# FPGA_POWER.net
KiCad netlist of a schematic drawn in Altium Designer
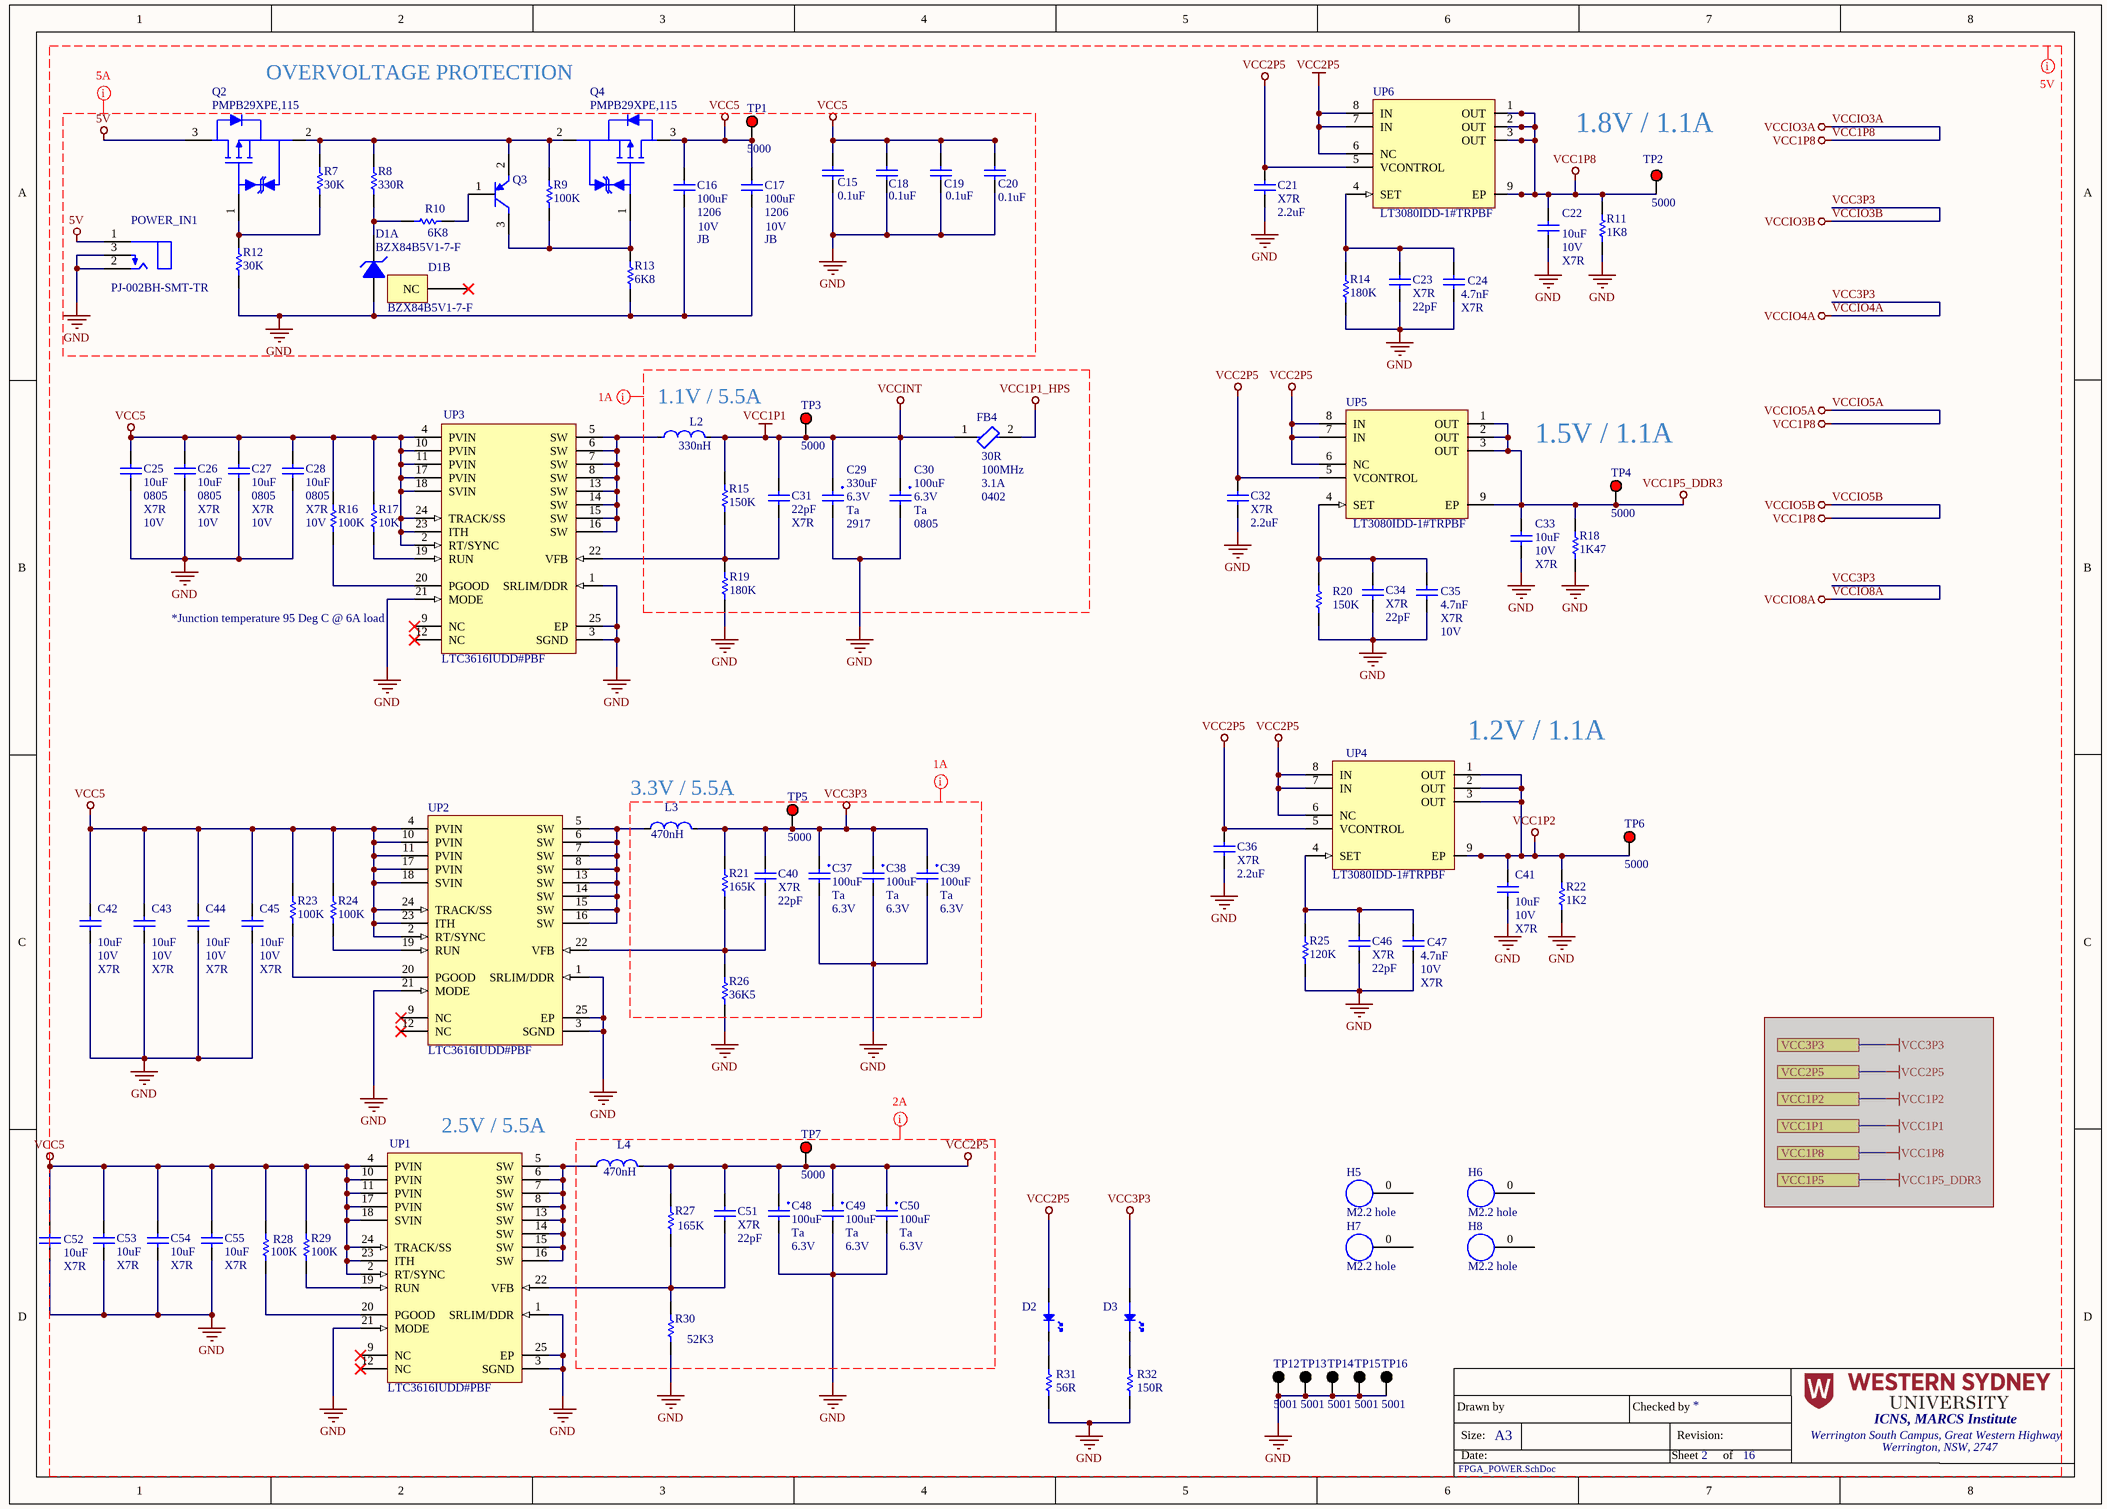
[diagram p0: FPGA_POWER.SchDoc]

(export (version "E")
  (design (tool "Eeschema 10.0.6"))
  (components
    (comp (ref "C15")
      (value "0.1uF")
      (footprint "CAP 0402 (1005)")
      (description "Cap Ceramic 0.1uF 10V X7R 20% SMD 0402 125°C Paper T/R")
      (fields
        (field (name "TOLERANCE") "20%")
        (field (name "Comment") "C0402C104M8RACTU")
        (field (name "SOURCE") "ICNS_PropheseeLib.SchLib")
      )
      (libsource (lib "Western Sydney University - ICNS") (part "Symbol"))
    )
    (comp (ref "C16")
      (value "100uF")
      (footprint "FP-C3216-160-0_3-IPC_A")
      (description "Cap Ceramic 100uF 10 V JB ±20 % Tolerance SMT 1206 Multilayer Ceramic Capacitor C Series")
      (fields
        (field (name "CASE/PACKAGE") "1206")
        (field (name "TOLERANCE") "20%")
        (field (name "VOLTAGE RATING") "10V")
        (field (name "DIELECTRIC") "JB")
        (field (name "Comment") "C3216JB1A107M160AC")
        (field (name "SOURCE") "ICNS_PropheseeLib.SchLib")
      )
      (libsource (lib "Western Sydney University - ICNS") (part "Symbol"))
    )
    (comp (ref "C17")
      (value "100uF")
      (footprint "FP-C3216-160-0_3-IPC_A")
      (description "Cap Ceramic 100uF 10 V JB ±20 % Tolerance SMT 1206 Multilayer Ceramic Capacitor C Series")
      (fields
        (field (name "CASE/PACKAGE") "1206")
        (field (name "TOLERANCE") "20%")
        (field (name "VOLTAGE RATING") "10V")
        (field (name "DIELECTRIC") "JB")
        (field (name "Comment") "C3216JB1A107M160AC")
        (field (name "SOURCE") "ICNS_PropheseeLib.SchLib")
      )
      (libsource (lib "Western Sydney University - ICNS") (part "Symbol"))
    )
    (comp (ref "C18")
      (value "0.1uF")
      (footprint "CAP 0402 (1005)")
      (description "Cap Ceramic 0.1uF 10V X7R 20% SMD 0402 125°C Paper T/R")
      (fields
        (field (name "TOLERANCE") "20%")
        (field (name "Comment") "C0402C104M8RACTU")
        (field (name "SOURCE") "ICNS_PropheseeLib.SchLib")
      )
      (libsource (lib "Western Sydney University - ICNS") (part "Symbol"))
    )
    (comp (ref "C19")
      (value "0.1uF")
      (footprint "CAP 0402 (1005)")
      (description "Cap Ceramic 0.1uF 10V X7R 20% SMD 0402 125°C Paper T/R")
      (fields
        (field (name "TOLERANCE") "20%")
        (field (name "Comment") "C0402C104M8RACTU")
        (field (name "SOURCE") "ICNS_PropheseeLib.SchLib")
      )
      (libsource (lib "Western Sydney University - ICNS") (part "Symbol"))
    )
    (comp (ref "C20")
      (value "0.1uF")
      (footprint "CAP 0402 (1005)")
      (description "Cap Ceramic 0.1uF 10V X7R 20% SMD 0402 125°C Paper T/R")
      (fields
        (field (name "TOLERANCE") "20%")
        (field (name "Comment") "C0402C104M8RACTU")
        (field (name "SOURCE") "ICNS_PropheseeLib.SchLib")
      )
      (libsource (lib "Western Sydney University - ICNS") (part "Symbol"))
    )
    (comp (ref "C21")
      (value "GRM155Z71A225KE01D")
      (footprint "CAP 0402 (1005)")
      (description "Multilayer Ceramic Capacitor 0402 10V X7R 2.2uf 10%Tol paper")
      (fields
        (field (name "DIELECTRIC") "X7R")
        (field (name "CAPACITANCE") "2.2uF")
        (field (name "MANUFACTURER") "Murata")
        (field (name "SOURCE") "ICNS_PropheseeLib.SchLib")
      )
      (libsource (lib "Western Sydney University - ICNS") (part "Symbol"))
    )
    (comp (ref "C22")
      (value "10uF")
      (footprint "CAP 0805 (2012)")
      (description "Cap Multilayer Ceramic 10 uF 10 V X7R ±10 % 0805 Surface Mount Capacitor")
      (fields
        (field (name "TOLERANCE") "10%")
        (field (name "DIELECTRIC") "X7R")
        (field (name "VOLTAGE RATING") "10V")
        (field (name "MANUFACTURER PART NUMBER") "GCM21BR71A106KE22K")
        (field (name "SOURCE") "ICNS_PropheseeLib.SchLib")
      )
      (libsource (lib "Western Sydney University - ICNS") (part "GCM21BR71A106KE22K"))
    )
    (comp (ref "C23")
      (value "22pF")
      (footprint "CAP 0402 (1005)")
      (description "Cap Ceramic 22pF 50V X7R 10% Pad SMD 0402 125C T/R")
      (fields
        (field (name "DIELECTRIC") "X7R")
        (field (name "TOLERANCE") "10%")
        (field (name "MANUFACTURER PART NUMBER") "C0402C220K5RACTU")
        (field (name "SOURCE") "ICNS_PropheseeLib.SchLib")
      )
      (libsource (lib "Western Sydney University - ICNS") (part "C0402C220K5RACTU"))
    )
    (comp (ref "C24")
      (value "4.7nF")
      (footprint "CAP 0402 (1005)")
      (description "Multilayer Ceramic Capacitor 0.0047uF 10V 10% 0402 Paper T/R")
      (fields
        (field (name "DIELECTRIC") "X7R")
        (field (name "MANUFACTURER PART NUMBER") "LMF105B7472KVHF")
        (field (name "MANUFACTURER") "Taiyo Yuden")
        (field (name "SOURCE") "ICNS_PropheseeLib.SchLib")
      )
      (libsource (lib "Western Sydney University - ICNS") (part "Symbol"))
    )
    (comp (ref "C25")
      (value "10uF")
      (footprint "CAP 0805 (2012)")
      (description "Cap Multilayer Ceramic 10 uF 10 V X7R ±10 % 0805 Surface Mount Capacitor")
      (fields
        (field (name "CASE CODE (IMPERIAL)") "0805")
        (field (name "DIELECTRIC") "X7R")
        (field (name "TOLERANCE") "10%")
        (field (name "VOLTAGE RATING") "10V")
        (field (name "MANUFACTURER PART NUMBER") "GCM21BR71A106KE22K")
        (field (name "SOURCE") "ICNS_PropheseeLib.SchLib")
      )
      (libsource (lib "Western Sydney University - ICNS") (part "GCM21BR71A106KE22K"))
    )
    (comp (ref "C26")
      (value "10uF")
      (footprint "CAP 0805 (2012)")
      (description "Cap Multilayer Ceramic 10 uF 10 V X7R ±10 % 0805 Surface Mount Capacitor")
      (fields
        (field (name "CASE CODE (IMPERIAL)") "0805")
        (field (name "DIELECTRIC") "X7R")
        (field (name "TOLERANCE") "10%")
        (field (name "VOLTAGE RATING") "10V")
        (field (name "MANUFACTURER PART NUMBER") "GCM21BR71A106KE22K")
        (field (name "SOURCE") "ICNS_PropheseeLib.SchLib")
      )
      (libsource (lib "Western Sydney University - ICNS") (part "GCM21BR71A106KE22K"))
    )
    (comp (ref "C27")
      (value "10uF")
      (footprint "CAP 0805 (2012)")
      (description "Cap Multilayer Ceramic 10 uF 10 V X7R ±10 % 0805 Surface Mount Capacitor")
      (fields
        (field (name "CASE CODE (IMPERIAL)") "0805")
        (field (name "DIELECTRIC") "X7R")
        (field (name "TOLERANCE") "10%")
        (field (name "VOLTAGE RATING") "10V")
        (field (name "MANUFACTURER PART NUMBER") "GCM21BR71A106KE22K")
        (field (name "SOURCE") "ICNS_PropheseeLib.SchLib")
      )
      (libsource (lib "Western Sydney University - ICNS") (part "GCM21BR71A106KE22K"))
    )
    (comp (ref "C28")
      (value "10uF")
      (footprint "CAP 0805 (2012)")
      (description "Cap Multilayer Ceramic 10 uF 10 V X7R ±10 % 0805 Surface Mount Capacitor")
      (fields
        (field (name "CASE CODE (IMPERIAL)") "0805")
        (field (name "DIELECTRIC") "X7R")
        (field (name "TOLERANCE") "10%")
        (field (name "VOLTAGE RATING") "10V")
        (field (name "MANUFACTURER PART NUMBER") "GCM21BR71A106KE22K")
        (field (name "SOURCE") "ICNS_PropheseeLib.SchLib")
      )
      (libsource (lib "Western Sydney University - ICNS") (part "GCM21BR71A106KE22K"))
    )
    (comp (ref "C29")
      (value "330uF")
      (footprint "CAPMP7343X31N")
      (description "Cap Tant Solid 330uF 6.3V D CASE 10% (7.3 X 4.3 X 2.8mm) SMD 7343-31 0.1 Ohm 125 C T/R")
      (fields
        (field (name "CASE CODE (IMPERIAL)") "2917")
        (field (name "DIELECTRIC") "Ta")
        (field (name "VOLTAGE RATING") "6.3V")
        (field (name "TOLERANCE") "20%")
        (field (name "VOLTAGE") "6.3V")
        (field (name "SOURCE") "ICNS_PropheseeLib.SchLib")
      )
      (libsource (lib "") (part "Symbol_2"))
    )
    (comp (ref "C30")
      (value "100uF")
      (footprint "CAPCP 0805 (2012)")
      (description "Cap Tant Solid 100uF 6.3V R CASE 20% (2 X 1.35 X 1.35mm) SMD 2012-15 5 Ohm 125°C Plastic T/R")
      (fields
        (field (name "CASE CODE (IMPERIAL)") "0805")
        (field (name "TOLERANCE") "20%")
        (field (name "VOLTAGE RATING") "6.3V")
        (field (name "DIELECTRIC") "Ta")
        (field (name "Comment") "TLCR107M006RTA")
        (field (name "SOURCE") "ICNS_PropheseeLib.SchLib")
      )
      (libsource (lib "") (part "Symbol_2"))
    )
    (comp (ref "C31")
      (value "22pF")
      (footprint "CAP 0402 (1005)")
      (description "Cap Ceramic 22pF 50V X7R 10% Pad SMD 0402 125C T/R")
      (fields
        (field (name "TOLERANCE") "10%")
        (field (name "DIELECTRIC") "X7R")
        (field (name "MANUFACTURER PART NUMBER") "C0402C220K5RACTU")
        (field (name "SOURCE") "ICNS_PropheseeLib.SchLib")
      )
      (libsource (lib "Western Sydney University - ICNS") (part "C0402C220K5RACTU"))
    )
    (comp (ref "C32")
      (value "GRM155Z71A225KE01D")
      (footprint "CAP 0402 (1005)")
      (description "Multilayer Ceramic Capacitor 0402 10V X7R 2.2uf 10%Tol paper")
      (fields
        (field (name "DIELECTRIC") "X7R")
        (field (name "CAPACITANCE") "2.2uF")
        (field (name "MANUFACTURER") "Murata")
        (field (name "SOURCE") "ICNS_PropheseeLib.SchLib")
      )
      (libsource (lib "Western Sydney University - ICNS") (part "Symbol"))
    )
    (comp (ref "C33")
      (value "10uF")
      (footprint "CAP 0805 (2012)")
      (description "Cap Multilayer Ceramic 10 uF 10 V X7R ±10 % 0805 Surface Mount Capacitor")
      (fields
        (field (name "TOLERANCE") "10%")
        (field (name "DIELECTRIC") "X7R")
        (field (name "VOLTAGE RATING") "10V")
        (field (name "MANUFACTURER PART NUMBER") "GCM21BR71A106KE22K")
        (field (name "SOURCE") "ICNS_PropheseeLib.SchLib")
      )
      (libsource (lib "Western Sydney University - ICNS") (part "GCM21BR71A106KE22K"))
    )
    (comp (ref "C34")
      (value "22pF")
      (footprint "CAP 0402 (1005)")
      (description "Cap Ceramic 22pF 50V X7R 10% Pad SMD 0402 125C T/R")
      (fields
        (field (name "DIELECTRIC") "X7R")
        (field (name "TOLERANCE") "10%")
        (field (name "MANUFACTURER PART NUMBER") "C0402C220K5RACTU")
        (field (name "SOURCE") "ICNS_PropheseeLib.SchLib")
      )
      (libsource (lib "Western Sydney University - ICNS") (part "C0402C220K5RACTU"))
    )
    (comp (ref "C35")
      (value "4.7nF")
      (footprint "CAP 0402 (1005)")
      (description "Multilayer Ceramic Capacitor 0.0047uF 10V 10% 0402 Paper T/R")
      (fields
        (field (name "DIELECTRIC") "X7R")
        (field (name "VOLTAGE RATING") "10V")
        (field (name "MANUFACTURER PART NUMBER") "LMF105B7472KVHF")
        (field (name "MANUFACTURER") "Taiyo Yuden")
        (field (name "SOURCE") "ICNS_PropheseeLib.SchLib")
      )
      (libsource (lib "Western Sydney University - ICNS") (part "Symbol"))
    )
    (comp (ref "C36")
      (value "GRM155Z71A225KE01D")
      (footprint "CAP 0402 (1005)")
      (description "Multilayer Ceramic Capacitor 0402 10V X7R 2.2uf 10%Tol paper")
      (fields
        (field (name "DIELECTRIC") "X7R")
        (field (name "CAPACITANCE") "2.2uF")
        (field (name "MANUFACTURER") "Murata")
        (field (name "SOURCE") "ICNS_PropheseeLib.SchLib")
      )
      (libsource (lib "Western Sydney University - ICNS") (part "Symbol"))
    )
    (comp (ref "C37")
      (value "100uF")
      (footprint "CAPCP 0805 (2012)")
      (description "Cap Tant Solid 100uF 6.3V R CASE 20% (2 X 1.35 X 1.35mm) SMD 2012-15 5 Ohm 125°C Plastic T/R")
      (fields
        (field (name "TOLERANCE") "20%")
        (field (name "DIELECTRIC") "Ta")
        (field (name "VOLTAGE RATING") "6.3V")
        (field (name "Comment") "TLCR107M006RTA")
        (field (name "SOURCE") "ICNS_PropheseeLib.SchLib")
      )
      (libsource (lib "") (part "Symbol_2"))
    )
    (comp (ref "C38")
      (value "100uF")
      (footprint "CAPCP 0805 (2012)")
      (description "Cap Tant Solid 100uF 6.3V R CASE 20% (2 X 1.35 X 1.35mm) SMD 2012-15 5 Ohm 125°C Plastic T/R")
      (fields
        (field (name "TOLERANCE") "20%")
        (field (name "DIELECTRIC") "Ta")
        (field (name "VOLTAGE RATING") "6.3V")
        (field (name "Comment") "TLCR107M006RTA")
        (field (name "SOURCE") "ICNS_PropheseeLib.SchLib")
      )
      (libsource (lib "") (part "Symbol_2"))
    )
    (comp (ref "C39")
      (value "100uF")
      (footprint "CAPCP 0805 (2012)")
      (description "Cap Tant Solid 100uF 6.3V R CASE 20% (2 X 1.35 X 1.35mm) SMD 2012-15 5 Ohm 125°C Plastic T/R")
      (fields
        (field (name "TOLERANCE") "20%")
        (field (name "DIELECTRIC") "Ta")
        (field (name "VOLTAGE RATING") "6.3V")
        (field (name "Comment") "TLCR107M006RTA")
        (field (name "SOURCE") "ICNS_PropheseeLib.SchLib")
      )
      (libsource (lib "") (part "Symbol_2"))
    )
    (comp (ref "C40")
      (value "22pF")
      (footprint "CAP 0402 (1005)")
      (description "Cap Ceramic 22pF 50V X7R 10% Pad SMD 0402 125C T/R")
      (fields
        (field (name "DIELECTRIC") "X7R")
        (field (name "TOLERANCE") "10%")
        (field (name "MANUFACTURER PART NUMBER") "C0402C220K5RACTU")
        (field (name "SOURCE") "ICNS_PropheseeLib.SchLib")
      )
      (libsource (lib "Western Sydney University - ICNS") (part "C0402C220K5RACTU"))
    )
    (comp (ref "C41")
      (value "10uF")
      (footprint "CAP 0805 (2012)")
      (description "Cap Multilayer Ceramic 10 uF 10 V X7R ±10 % 0805 Surface Mount Capacitor")
      (fields
        (field (name "TOLERANCE") "10%")
        (field (name "DIELECTRIC") "X7R")
        (field (name "VOLTAGE RATING") "10V")
        (field (name "MANUFACTURER PART NUMBER") "GCM21BR71A106KE22K")
        (field (name "SOURCE") "ICNS_PropheseeLib.SchLib")
      )
      (libsource (lib "Western Sydney University - ICNS") (part "GCM21BR71A106KE22K"))
    )
    (comp (ref "C42")
      (value "10uF")
      (footprint "CAP 0805 (2012)")
      (description "Cap Multilayer Ceramic 10 uF 10 V X7R ±10 % 0805 Surface Mount Capacitor")
      (fields
        (field (name "DIELECTRIC") "X7R")
        (field (name "TOLERANCE") "10%")
        (field (name "VOLTAGE RATING") "10V")
        (field (name "MANUFACTURER PART NUMBER") "GCM21BR71A106KE22K")
        (field (name "SOURCE") "ICNS_PropheseeLib.SchLib")
      )
      (libsource (lib "Western Sydney University - ICNS") (part "GCM21BR71A106KE22K"))
    )
    (comp (ref "C43")
      (value "10uF")
      (footprint "CAP 0805 (2012)")
      (description "Cap Multilayer Ceramic 10 uF 10 V X7R ±10 % 0805 Surface Mount Capacitor")
      (fields
        (field (name "DIELECTRIC") "X7R")
        (field (name "TOLERANCE") "10%")
        (field (name "VOLTAGE RATING") "10V")
        (field (name "MANUFACTURER PART NUMBER") "GCM21BR71A106KE22K")
        (field (name "SOURCE") "ICNS_PropheseeLib.SchLib")
      )
      (libsource (lib "Western Sydney University - ICNS") (part "GCM21BR71A106KE22K"))
    )
    (comp (ref "C44")
      (value "10uF")
      (footprint "CAP 0805 (2012)")
      (description "Cap Multilayer Ceramic 10 uF 10 V X7R ±10 % 0805 Surface Mount Capacitor")
      (fields
        (field (name "DIELECTRIC") "X7R")
        (field (name "TOLERANCE") "10%")
        (field (name "VOLTAGE RATING") "10V")
        (field (name "MANUFACTURER PART NUMBER") "GCM21BR71A106KE22K")
        (field (name "SOURCE") "ICNS_PropheseeLib.SchLib")
      )
      (libsource (lib "Western Sydney University - ICNS") (part "GCM21BR71A106KE22K"))
    )
    (comp (ref "C45")
      (value "10uF")
      (footprint "CAP 0805 (2012)")
      (description "Cap Multilayer Ceramic 10 uF 10 V X7R ±10 % 0805 Surface Mount Capacitor")
      (fields
        (field (name "DIELECTRIC") "X7R")
        (field (name "TOLERANCE") "10%")
        (field (name "VOLTAGE RATING") "10V")
        (field (name "MANUFACTURER PART NUMBER") "GCM21BR71A106KE22K")
        (field (name "SOURCE") "ICNS_PropheseeLib.SchLib")
      )
      (libsource (lib "Western Sydney University - ICNS") (part "GCM21BR71A106KE22K"))
    )
    (comp (ref "C46")
      (value "22pF")
      (footprint "CAP 0402 (1005)")
      (description "Cap Ceramic 22pF 50V X7R 10% Pad SMD 0402 125C T/R")
      (fields
        (field (name "DIELECTRIC") "X7R")
        (field (name "TOLERANCE") "10%")
        (field (name "MANUFACTURER PART NUMBER") "C0402C220K5RACTU")
        (field (name "SOURCE") "ICNS_PropheseeLib.SchLib")
      )
      (libsource (lib "Western Sydney University - ICNS") (part "C0402C220K5RACTU"))
    )
    (comp (ref "C47")
      (value "4.7nF")
      (footprint "CAP 0402 (1005)")
      (description "Multilayer Ceramic Capacitor 0.0047uF 10V 10% 0402 Paper T/R")
      (fields
        (field (name "DIELECTRIC") "X7R")
        (field (name "VOLTAGE RATING") "10V")
        (field (name "MANUFACTURER PART NUMBER") "LMF105B7472KVHF")
        (field (name "MANUFACTURER") "Taiyo Yuden")
        (field (name "SOURCE") "ICNS_PropheseeLib.SchLib")
      )
      (libsource (lib "Western Sydney University - ICNS") (part "Symbol"))
    )
    (comp (ref "C48")
      (value "100uF")
      (footprint "CAPCP 0805 (2012)")
      (description "Cap Tant Solid 100uF 6.3V R CASE 20% (2 X 1.35 X 1.35mm) SMD 2012-15 5 Ohm 125°C Plastic T/R")
      (fields
        (field (name "TOLERANCE") "20%")
        (field (name "DIELECTRIC") "Ta")
        (field (name "VOLTAGE RATING") "6.3V")
        (field (name "Comment") "TLCR107M006RTA")
        (field (name "SOURCE") "ICNS_PropheseeLib.SchLib")
      )
      (libsource (lib "") (part "Symbol_2"))
    )
    (comp (ref "C49")
      (value "100uF")
      (footprint "CAPCP 0805 (2012)")
      (description "Cap Tant Solid 100uF 6.3V R CASE 20% (2 X 1.35 X 1.35mm) SMD 2012-15 5 Ohm 125°C Plastic T/R")
      (fields
        (field (name "TOLERANCE") "20%")
        (field (name "DIELECTRIC") "Ta")
        (field (name "VOLTAGE RATING") "6.3V")
        (field (name "Comment") "TLCR107M006RTA")
        (field (name "SOURCE") "ICNS_PropheseeLib.SchLib")
      )
      (libsource (lib "") (part "Symbol_2"))
    )
    (comp (ref "C50")
      (value "100uF")
      (footprint "CAPCP 0805 (2012)")
      (description "Cap Tant Solid 100uF 6.3V R CASE 20% (2 X 1.35 X 1.35mm) SMD 2012-15 5 Ohm 125°C Plastic T/R")
      (fields
        (field (name "TOLERANCE") "20%")
        (field (name "DIELECTRIC") "Ta")
        (field (name "VOLTAGE RATING") "6.3V")
        (field (name "Comment") "TLCR107M006RTA")
        (field (name "SOURCE") "ICNS_PropheseeLib.SchLib")
      )
      (libsource (lib "") (part "Symbol_2"))
    )
    (comp (ref "C51")
      (value "22pF")
      (footprint "CAP 0402 (1005)")
      (description "Cap Ceramic 22pF 50V X7R 10% Pad SMD 0402 125C T/R")
      (fields
        (field (name "DIELECTRIC") "X7R")
        (field (name "TOLERANCE") "10%")
        (field (name "MANUFACTURER PART NUMBER") "C0402C220K5RACTU")
        (field (name "SOURCE") "ICNS_PropheseeLib.SchLib")
      )
      (libsource (lib "Western Sydney University - ICNS") (part "C0402C220K5RACTU"))
    )
    (comp (ref "C52")
      (value "10uF")
      (footprint "CAP 0805 (2012)")
      (description "0805 10 uF 10 V ±10 % Tolerance X7R Surface Mount Multilayer Ceramic Capacitor")
      (fields
        (field (name "DIELECTRIC") "X7R")
        (field (name "TOLERANCE") "10%")
        (field (name "MANUFACTURER PART NUMBER") "GCM21BR71A106KE22K")
        (field (name "SOURCE") "ICNS_PropheseeLib.SchLib")
      )
      (libsource (lib "Western Sydney University - ICNS") (part "GCM21BR71A106KE22K"))
    )
    (comp (ref "C53")
      (value "10uF")
      (footprint "CAP 0805 (2012)")
      (description "0805 10 uF 10 V ±10 % Tolerance X7R Surface Mount Multilayer Ceramic Capacitor")
      (fields
        (field (name "DIELECTRIC") "X7R")
        (field (name "TOLERANCE") "10%")
        (field (name "MANUFACTURER PART NUMBER") "GCM21BR71A106KE22K")
        (field (name "SOURCE") "ICNS_PropheseeLib.SchLib")
      )
      (libsource (lib "Western Sydney University - ICNS") (part "GCM21BR71A106KE22K"))
    )
    (comp (ref "C54")
      (value "10uF")
      (footprint "CAP 0805 (2012)")
      (description "0805 10 uF 10 V ±10 % Tolerance X7R Surface Mount Multilayer Ceramic Capacitor")
      (fields
        (field (name "DIELECTRIC") "X7R")
        (field (name "TOLERANCE") "10%")
        (field (name "MANUFACTURER PART NUMBER") "GCM21BR71A106KE22K")
        (field (name "SOURCE") "ICNS_PropheseeLib.SchLib")
      )
      (libsource (lib "Western Sydney University - ICNS") (part "GCM21BR71A106KE22K"))
    )
    (comp (ref "C55")
      (value "10uF")
      (footprint "CAP 0805 (2012)")
      (description "0805 10 uF 10 V ±10 % Tolerance X7R Surface Mount Multilayer Ceramic Capacitor")
      (fields
        (field (name "DIELECTRIC") "X7R")
        (field (name "TOLERANCE") "10%")
        (field (name "MANUFACTURER PART NUMBER") "GCM21BR71A106KE22K")
        (field (name "SOURCE") "ICNS_PropheseeLib.SchLib")
      )
      (libsource (lib "Western Sydney University - ICNS") (part "GCM21BR71A106KE22K"))
    )
    (comp (ref "D1")
      (value "BZX84B5V1-7-F")
      (footprint "FP-SOT23-IPC_A")
      (description "Diode Zener Single 5.1V 2% 350mW 3-Pin SOT-23 T/R")
      (fields
        (field (name "TOLERANCE") "2%")
        (field (name "MANUFACTURER") "Diodes")
        (field (name "SOURCE") "ICNS_PropheseeLib.SchLib")
      )
      (libsource (lib "") (part "BZX84B5V1-7-F_1"))
    )
    (comp (ref "D2")
      (value "150060SS75000")
      (footprint "DIOC 0603 (1608)")
      (description "Led, Red, 630 Nm, 1.9 V, 20mA, 30 Ma, 60 Mcd Rohs Compliant: Yes")
      (fields (field (name "SOURCE") "ICNS_PropheseeLib.SchLib"))
      (libsource (lib "Western Sydney University - ICNS") (part "150060SS75000"))
    )
    (comp (ref "D3")
      (value "150060SS75000")
      (footprint "DIOC 0603 (1608)")
      (description "Led, Red, 630 Nm, 1.9 V, 20mA, 30 Ma, 60 Mcd Rohs Compliant: Yes")
      (fields (field (name "SOURCE") "ICNS_PropheseeLib.SchLib"))
      (libsource (lib "Western Sydney University - ICNS") (part "150060SS75000"))
    )
    (comp (ref "FB4")
      (value "BLM15KD300SN1D")
      (footprint "FP-BLM15-0_05-d1_2-IPC_A")
      (description "Ferrite Beads Multi-Layer 30Ohm 25% 100MHz 3.1A 0.017Ohm DCR 0402 T/R")
      (fields
        (field (name "TEST FREQUENCY") "100MHz")
        (field (name "IMPEDANCE") "30R")
        (field (name "CASE CODE (IMPERIAL)") "0402")
        (field (name "MAX CURRENT RATING") "3.1A")
        (field (name "MANUFACTURER") "Murata")
        (field (name "SOURCE") "ICNS_PropheseeLib.SchLib")
      )
      (libsource (lib "Western Sydney University - ICNS") (part "BLM15KD300SN1D"))
    )
    (comp (ref "H5")
      (value "M2.2 hole")
      (footprint "M2.2 hole")
      (description "M2.2 through hole not plated")
      (fields (field (name "SOURCE") "ICNS_PropheseeLib.SchLib"))
      (libsource (lib "Western Sydney University - ICNS") (part "M2.2 hole"))
    )
    (comp (ref "H6")
      (value "M2.2 hole")
      (footprint "M2.2 hole")
      (description "M2.2 through hole not plated")
      (fields (field (name "SOURCE") "ICNS_PropheseeLib.SchLib"))
      (libsource (lib "Western Sydney University - ICNS") (part "M2.2 hole"))
    )
    (comp (ref "H7")
      (value "M2.2 hole")
      (footprint "M2.2 hole")
      (description "M2.2 through hole not plated")
      (fields (field (name "SOURCE") "ICNS_PropheseeLib.SchLib"))
      (libsource (lib "Western Sydney University - ICNS") (part "M2.2 hole"))
    )
    (comp (ref "H8")
      (value "M2.2 hole")
      (footprint "M2.2 hole")
      (description "M2.2 through hole not plated")
      (fields (field (name "SOURCE") "ICNS_PropheseeLib.SchLib"))
      (libsource (lib "Western Sydney University - ICNS") (part "M2.2 hole"))
    )
    (comp (ref "L2")
      (value "330nH")
      (footprint "FP-IHLP-2525CZ-FP_2_413x3-MFG")
      (description "Inductor High Current Shielded Wirewound 330nH 20% 100KHz 20A 3.9mOhm DCR 2525 T/R")
      (fields (field (name "TOLERANCE") "20%") (field (name "Comment") "IHLP2525CZERR33M01"))
      (libsource (lib "Western Sydney University - ICNS") (part "725321dda6339637d4d059423bc1c3c"))
    )
    (comp (ref "L3")
      (value "470nH")
      (footprint "INDM6965X30N")
      (description "Power Choke Shielded Wirewound 0.47uH 20% 100KHz Powdered Iron 17.5A 0.0042Ohm DCR 2525 T/R")
      (fields
        (field (name "TOLERANCE") "20%")
        (field (name "Comment") "IHLP2525CZETR47M01")
        (field (name "SOURCE") "ICNS_PropheseeLib.SchLib")
      )
      (libsource (lib "Western Sydney University - ICNS") (part "IHLP2525CZETR47M01"))
    )
    (comp (ref "L4")
      (value "470nH")
      (footprint "INDM6965X30N")
      (description "Power Choke Shielded Wirewound 0.47uH 20% 100KHz Powdered Iron 17.5A 0.0042Ohm DCR 2525 T/R")
      (fields
        (field (name "TOLERANCE") "20%")
        (field (name "Comment") "IHLP2525CZETR47M01")
        (field (name "SOURCE") "ICNS_PropheseeLib.SchLib")
      )
      (libsource (lib "Western Sydney University - ICNS") (part "IHLP2525CZETR47M01"))
    )
    (comp (ref "POWER_IN1")
      (value "PJ-002BH-SMT-TR")
      (footprint "FP-PJ-002BH-SMT-TR-MFG")
      (description "Power Barrel Connector Jack 2.50mm ID (0.098\"), 5.50mm OD (0.217\") Surface Mount, Right Angle")
      (fields (field (name "MANUFACTURER") "CUI") (field (name "SOURCE") "ICNS_PropheseeLib.SchLib"))
      (libsource (lib "Western Sydney University - ICNS") (part "PJ-002BH-SMT-TR"))
    )
    (comp (ref "Q2")
      (value "PMPB29XPE,115")
      (footprint "DFN2020MD-6")
      (description "PMPB29XPE - 20 V, single P-channel Trench MOSFET")
      (fields (field (name "MANUFACTURER") "Nexperia") (field (name "SOURCE") "ICNS_PropheseeLib.SchLib"))
      (libsource (lib "Western Sydney University - ICNS") (part "PMPB29XPE,115"))
    )
    (comp (ref "Q3")
      (value "CMP-007-000000-1")
      (footprint "FP-SOT23-IPC_A")
      (description "TRANS PNP 25V 1.5A SOT23")
      (fields (field (name "SOURCE") "ICNS_PropheseeLib.SchLib"))
      (libsource (lib "Western Sydney University - ICNS") (part "MMSS8550-H-TP"))
    )
    (comp (ref "Q4")
      (value "PMPB29XPE,115")
      (footprint "DFN2020MD-6")
      (description "PMPB29XPE - 20 V, single P-channel Trench MOSFET")
      (fields (field (name "MANUFACTURER") "Nexperia") (field (name "SOURCE") "ICNS_PropheseeLib.SchLib"))
      (libsource (lib "Western Sydney University - ICNS") (part "PMPB29XPE,115"))
    )
    (comp (ref "R7")
      (value "30K")
      (footprint "RES 0402 (1005)")
      (fields
        (field (name "TOLERANCE") "1%")
        (field (name "Comment") "RCS040230K0FKED")
        (field (name "SOURCE") "ICNS_PropheseeLib.SchLib")
      )
      (libsource (lib "") (part "Symbol_1"))
    )
    (comp (ref "R8")
      (value "330R")
      (footprint "RES 0402 (1005)")
      (description "Res Thick Film 0402 330 Ohm 1% 0.2W ±100ppm/°C Molded SMD SMD Paper T/R")
      (fields
        (field (name "TOLERANCE") "1%")
        (field (name "Comment") "CRCW0402330RFKEDHP")
        (field (name "SOURCE") "ICNS_PropheseeLib.SchLib")
      )
      (libsource (lib "") (part "Symbol_1"))
    )
    (comp (ref "R9")
      (value "100K")
      (footprint "RES 0402 (1005)")
      (description "Res Thick Film 0402 100K Ohm 1% 0.2W(1/5W) ±100ppm/C Pad SMD Automotive T/R")
      (fields
        (field (name "TOLERANCE") "1%")
        (field (name "Comment") "CRCW0402100KFKEDHP")
        (field (name "SOURCE") "ICNS_PropheseeLib.SchLib")
      )
      (libsource (lib "") (part "Symbol_1"))
    )
    (comp (ref "R10")
      (value "6K8")
      (footprint "RES 0402 (1005)")
      (description "Res Thick Film 0402 6.8K Ohm 1% 0.2W(1/5W) ±100ppm/°C Pad SMD Automotive T/R")
      (fields
        (field (name "TOLERANCE") "1%")
        (field (name "Comment") "CRCW04026K80FKEDHP")
        (field (name "SOURCE") "ICNS_PropheseeLib.SchLib")
      )
      (libsource (lib "") (part "Symbol_1"))
    )
    (comp (ref "R11")
      (value "1K8")
      (footprint "RES 0402 (1005)")
      (description "Res Thick Film 0402 1.8K Ohm 1% 0.2W(1/5W) ±100ppm/°C Pad SMD Automotive T/R")
      (fields
        (field (name "TOLERANCE") "1%")
        (field (name "Comment") "CRCW04021K80FKEDHP")
        (field (name "SOURCE") "ICNS_PropheseeLib.SchLib")
      )
      (libsource (lib "") (part "Symbol_1"))
    )
    (comp (ref "R12")
      (value "30K")
      (footprint "RES 0402 (1005)")
      (fields
        (field (name "TOLERANCE") "1%")
        (field (name "Comment") "RCS040230K0FKED")
        (field (name "SOURCE") "ICNS_PropheseeLib.SchLib")
      )
      (libsource (lib "") (part "Symbol_1"))
    )
    (comp (ref "R13")
      (value "6K8")
      (footprint "RES 0402 (1005)")
      (description "Res Thick Film 0402 6.8K Ohm 1% 0.2W(1/5W) ±100ppm/°C Pad SMD Automotive T/R")
      (fields
        (field (name "TOLERANCE") "1%")
        (field (name "Comment") "CRCW04026K80FKEDHP")
        (field (name "SOURCE") "ICNS_PropheseeLib.SchLib")
      )
      (libsource (lib "") (part "Symbol_1"))
    )
    (comp (ref "R14")
      (value "180K")
      (footprint "RES 0402 (1005)")
      (fields
        (field (name "TOLERANCE") "1%")
        (field (name "Comment") "RCS0402180KFKED")
        (field (name "SOURCE") "ICNS_PropheseeLib.SchLib")
      )
      (libsource (lib "") (part "Symbol_1"))
    )
    (comp (ref "R15")
      (value "150K")
      (footprint "RES 0402 (1005)")
      (description "Res Thick Film 0402 150K Ohm 1% 1/16W ±100ppm/°C Molded SMD SMD Paper T/R")
      (fields
        (field (name "TOLERANCE") "1%")
        (field (name "Comment") "CRCW0402150KFKED")
        (field (name "SOURCE") "ICNS_PropheseeLib.SchLib")
      )
      (libsource (lib "") (part "Symbol_1"))
    )
    (comp (ref "R16")
      (value "100K")
      (footprint "RES 0402 (1005)")
      (description "Res Thick Film 0402 100K Ohm 1% 0.2W(1/5W) ±100ppm/C Pad SMD Automotive T/R")
      (fields
        (field (name "TOLERANCE") "1%")
        (field (name "Comment") "CRCW0402100KFKEDHP")
        (field (name "SOURCE") "ICNS_PropheseeLib.SchLib")
      )
      (libsource (lib "") (part "Symbol_1"))
    )
    (comp (ref "R17")
      (value "10K")
      (footprint "RES 0402 (1005)")
      (description "Res Thick Film 0402 10K Ohm 1% 0.2W(1/5W) ±100ppm/°C Pad SMD Automotive Medical T/R")
      (fields
        (field (name "TOLERANCE") "1%")
        (field (name "Comment") "RCS040210K0FKED")
        (field (name "SOURCE") "ICNS_PropheseeLib.SchLib")
      )
      (libsource (lib "Western Sydney University - ICNS") (part "RCS040210K0FKED"))
    )
    (comp (ref "R18")
      (value "1K47")
      (footprint "RES 0402 (1005)")
      (description "Res Thick Film 0402 1.47K Ohm 1% 1/16W ±100ppm/°C Molded SMD SMD Paper T/R")
      (fields
        (field (name "TOLERANCE") "1%")
        (field (name "Comment") "CRCW04021K47FKED")
        (field (name "SOURCE") "ICNS_PropheseeLib.SchLib")
      )
      (libsource (lib "") (part "Symbol_1"))
    )
    (comp (ref "R19")
      (value "180K")
      (footprint "RES 0402 (1005)")
      (fields
        (field (name "TOLERANCE") "1%")
        (field (name "Comment") "RCS0402180KFKED")
        (field (name "SOURCE") "ICNS_PropheseeLib.SchLib")
      )
      (libsource (lib "Western Sydney University - ICNS") (part "CMP-006-000001-1"))
    )
    (comp (ref "R20")
      (value "150K")
      (footprint "RES 0402 (1005)")
      (description "Res Thick Film 0402 150K Ohm 1% 1/16W ±100ppm/°C Molded SMD SMD Paper T/R")
      (fields
        (field (name "TOLERANCE") "1%")
        (field (name "Comment") "CRCW0402150KFKED")
        (field (name "SOURCE") "ICNS_PropheseeLib.SchLib")
      )
      (libsource (lib "") (part "Symbol_1"))
    )
    (comp (ref "R21")
      (value "165K")
      (footprint "RES 0402 (1005)")
      (description "Res Thick Film 0402 165K Ohm 1% 1/16W ±100ppm/°C Molded SMD Paper T/R")
      (fields
        (field (name "TOLERANCE") "1%")
        (field (name "Comment") "RC0402FR-07165KL")
        (field (name "SOURCE") "ICNS_PropheseeLib.SchLib")
      )
      (libsource (lib "Western Sydney University - ICNS") (part "RC0402FR-07165KL"))
    )
    (comp (ref "R22")
      (value "1K2")
      (footprint "RES 0402 (1005)")
      (description "Res Thick Film 0402 1.2K Ohm 1% 0.2W(1/5W) ±100ppm/°C Pad SMD Automotive T/R")
      (fields
        (field (name "TOLERANCE") "1%")
        (field (name "Comment") "CRCW04021K20FKEDHP")
        (field (name "SOURCE") "ICNS_PropheseeLib.SchLib")
      )
      (libsource (lib "") (part "Symbol_1"))
    )
    (comp (ref "R23")
      (value "100K")
      (footprint "RES 0402 (1005)")
      (description "Res Thick Film 0402 100K Ohm 1% 0.2W(1/5W) ±100ppm/C Pad SMD Automotive T/R")
      (fields
        (field (name "TOLERANCE") "1%")
        (field (name "Comment") "CRCW0402100KFKEDHP")
        (field (name "SOURCE") "ICNS_PropheseeLib.SchLib")
      )
      (libsource (lib "") (part "Symbol_1"))
    )
    (comp (ref "R24")
      (value "100K")
      (footprint "RES 0402 (1005)")
      (description "Res Thick Film 0402 100K Ohm 1% 0.2W(1/5W) ±100ppm/C Pad SMD Automotive T/R")
      (fields
        (field (name "TOLERANCE") "1%")
        (field (name "Comment") "CRCW0402100KFKEDHP")
        (field (name "SOURCE") "ICNS_PropheseeLib.SchLib")
      )
      (libsource (lib "") (part "Symbol_1"))
    )
    (comp (ref "R25")
      (value "120K")
      (footprint "RES 0402 (1005)")
      (description "Res Thick Film 0402 120K Ohm 1% 0.2W ±100ppm/°C Molded SMD SMD Paper T/R")
      (fields
        (field (name "TOLERANCE") "1%")
        (field (name "Comment") "CRCW0402120KFKEDHP")
        (field (name "SOURCE") "ICNS_PropheseeLib.SchLib")
      )
      (libsource (lib "") (part "Symbol_1"))
    )
    (comp (ref "R26")
      (value "36K5")
      (footprint "RES 0402 (1005)")
      (fields
        (field (name "TOLERANCE") "1%")
        (field (name "Comment") "AC0402FR-0736K5L")
        (field (name "SOURCE") "ICNS_PropheseeLib.SchLib")
      )
      (libsource (lib "") (part "Symbol_1"))
    )
    (comp (ref "R27")
      (value "165K")
      (footprint "RES 0402 (1005)")
      (description "Res Thick Film 0402 165K Ohm 1% 1/16W ±100ppm/°C Molded SMD Paper T/R")
      (fields
        (field (name "TOLERANCE") "1%")
        (field (name "Comment") "RC0402FR-07165KL")
        (field (name "SOURCE") "ICNS_PropheseeLib.SchLib")
      )
      (libsource (lib "Western Sydney University - ICNS") (part "RC0402FR-07165KL"))
    )
    (comp (ref "R28")
      (value "100K")
      (footprint "RES 0402 (1005)")
      (description "Res Thick Film 0402 100K Ohm 1% 0.2W(1/5W) ±100ppm/C Pad SMD Automotive T/R")
      (fields
        (field (name "TOLERANCE") "1%")
        (field (name "Comment") "CRCW0402100KFKEDHP")
        (field (name "SOURCE") "ICNS_PropheseeLib.SchLib")
      )
      (libsource (lib "") (part "Symbol_1"))
    )
    (comp (ref "R29")
      (value "100K")
      (footprint "RES 0402 (1005)")
      (description "Res Thick Film 0402 100K Ohm 1% 0.2W(1/5W) ±100ppm/C Pad SMD Automotive T/R")
      (fields
        (field (name "TOLERANCE") "1%")
        (field (name "Comment") "CRCW0402100KFKEDHP")
        (field (name "SOURCE") "ICNS_PropheseeLib.SchLib")
      )
      (libsource (lib "") (part "Symbol_1"))
    )
    (comp (ref "R30")
      (value "52K3")
      (footprint "RES 0402 (1005)")
      (description "Res Thick Film 0402 52.3K Ohm 1% 0.2W(1/5W) ±100ppm/°C Automotive AEC-Q200, Pulse Withstanding")
      (fields
        (field (name "TOLERANCE") "1%")
        (field (name "Comment") "RCS040252K3FKED")
        (field (name "SOURCE") "ICNS_PropheseeLib.SchLib")
      )
      (libsource (lib "") (part "Symbol_1"))
    )
    (comp (ref "R31")
      (value "56R")
      (footprint "RES 0603 (1608)")
      (description "Res Thick Film 0603 56 Ohms ±1% 0.125W, 1/8W Chip Resistor (1608 Metric) Automotive AEC-Q200")
      (fields
        (field (name "TOLERANCE") "1%")
        (field (name "MANUFACTURER PART NUMBER") "ERJH3EF56R0V")
        (field (name "SOURCE") "ICNS_PropheseeLib.SchLib")
      )
      (libsource (lib "Western Sydney University - ICNS") (part "ERJH3EF56R0V"))
    )
    (comp (ref "R32")
      (value "150R")
      (footprint "RES 0603 (1608)")
      (description "Res Thick Film 0603 150 Ohm 1% Paper T/R Automotive Grade")
      (fields
        (field (name "TOLERANCE") "1%")
        (field (name "MANUFACTURER") "Yageo")
        (field (name "SOURCE") "ICNS_PropheseeLib.SchLib")
      )
      (libsource (lib "Western Sydney University - ICNS") (part "AC0603FR-10150RL"))
    )
    (comp (ref "TP1")
      (value "5000")
      (footprint "FP-5000-MFG")
      (fields
        (field (name "MANUFACTURER") "Keystone Electronics")
        (field (name "SOURCE") "ICNS_PropheseeLib.SchLib")
      )
      (libsource (lib "Western Sydney University - ICNS") (part "5000"))
    )
    (comp (ref "TP2")
      (value "5000")
      (footprint "FP-5000-MFG")
      (fields
        (field (name "MANUFACTURER") "Keystone Electronics")
        (field (name "SOURCE") "ICNS_PropheseeLib.SchLib")
      )
      (libsource (lib "Western Sydney University - ICNS") (part "5000"))
    )
    (comp (ref "TP3")
      (value "5000")
      (footprint "FP-5000-MFG")
      (fields
        (field (name "MANUFACTURER") "Keystone Electronics")
        (field (name "SOURCE") "ICNS_PropheseeLib.SchLib")
      )
      (libsource (lib "Western Sydney University - ICNS") (part "5000"))
    )
    (comp (ref "TP4")
      (value "5000")
      (footprint "FP-5000-MFG")
      (fields
        (field (name "MANUFACTURER") "Keystone Electronics")
        (field (name "SOURCE") "ICNS_PropheseeLib.SchLib")
      )
      (libsource (lib "Western Sydney University - ICNS") (part "5000"))
    )
    (comp (ref "TP5")
      (value "5000")
      (footprint "FP-5000-MFG")
      (fields
        (field (name "MANUFACTURER") "Keystone Electronics")
        (field (name "SOURCE") "ICNS_PropheseeLib.SchLib")
      )
      (libsource (lib "Western Sydney University - ICNS") (part "5000"))
    )
    (comp (ref "TP6")
      (value "5000")
      (footprint "FP-5000-MFG")
      (fields
        (field (name "MANUFACTURER") "Keystone Electronics")
        (field (name "SOURCE") "ICNS_PropheseeLib.SchLib")
      )
      (libsource (lib "Western Sydney University - ICNS") (part "5000"))
    )
    (comp (ref "TP7")
      (value "5000")
      (footprint "FP-5000-MFG")
      (fields
        (field (name "MANUFACTURER") "Keystone Electronics")
        (field (name "SOURCE") "ICNS_PropheseeLib.SchLib")
      )
      (libsource (lib "Western Sydney University - ICNS") (part "5000"))
    )
    (comp (ref "TP12")
      (value "5001")
      (footprint "FP-5001-MFG")
      (description "TEST POINT PC MINI .040D BLACK")
      (libsource (lib "Western Sydney University - ICNS") (part "1e4615820a309e3ce90f9e6d957b7fa"))
    )
    (comp (ref "TP13")
      (value "5001")
      (footprint "FP-5001-MFG")
      (description "TEST POINT PC MINI .040D BLACK")
      (libsource (lib "Western Sydney University - ICNS") (part "1e4615820a309e3ce90f9e6d957b7fa"))
    )
    (comp (ref "TP14")
      (value "5001")
      (footprint "FP-5001-MFG")
      (description "TEST POINT PC MINI .040D BLACK")
      (libsource (lib "Western Sydney University - ICNS") (part "1e4615820a309e3ce90f9e6d957b7fa"))
    )
    (comp (ref "TP15")
      (value "5001")
      (footprint "FP-5001-MFG")
      (description "TEST POINT PC MINI .040D BLACK")
      (libsource (lib "Western Sydney University - ICNS") (part "1e4615820a309e3ce90f9e6d957b7fa"))
    )
    (comp (ref "TP16")
      (value "5001")
      (footprint "FP-5001-MFG")
      (description "TEST POINT PC MINI .040D BLACK")
      (libsource (lib "Western Sydney University - ICNS") (part "1e4615820a309e3ce90f9e6d957b7fa"))
    )
    (comp (ref "UP1")
      (value "LTC3616IUDD#PBF")
      (footprint "LT-UDD-24_N")
      (description "Buck Switching Regulator IC Positive Adjustable 0.6V 1 Output 6A 24-WFQFN Exposed Pad")
      (fields
        (field (name "MANUFACTURER") "Analog Devices / Linear Technology")
        (field (name "SOURCE") "ICNS_PropheseeLib.SchLib")
      )
      (libsource (lib "Western Sydney University - ICNS") (part "LTC3616IUDD#PBF"))
    )
    (comp (ref "UP2")
      (value "LTC3616IUDD#PBF")
      (footprint "LT-UDD-24_N")
      (description "Buck Switching Regulator IC Positive Adjustable 0.6V 1 Output 6A 24-WFQFN Exposed Pad")
      (fields
        (field (name "MANUFACTURER") "Analog Devices / Linear Technology")
        (field (name "SOURCE") "ICNS_PropheseeLib.SchLib")
      )
      (libsource (lib "Western Sydney University - ICNS") (part "LTC3616IUDD#PBF"))
    )
    (comp (ref "UP3")
      (value "LTC3616IUDD#PBF")
      (footprint "LT-UDD-24_N")
      (description "Buck Switching Regulator IC Positive Adjustable 0.6V 1 Output 6A 24-WFQFN Exposed Pad")
      (fields
        (field (name "MANUFACTURER") "Analog Devices / Linear Technology")
        (field (name "SOURCE") "ICNS_PropheseeLib.SchLib")
      )
      (libsource (lib "Western Sydney University - ICNS") (part "LTC3616IUDD#PBF"))
    )
    (comp (ref "UP4")
      (value "LT3080IDD-1#TRPBF")
      (footprint "LT-DD-8_V")
      (description "Linear Voltage Regulator IC Positive Adjustable 1 Output 1.1A 8-DFN (3x3)")
      (fields
        (field (name "MANUFACTURER") "Analog Devices / Linear Technology")
        (field (name "SOURCE") "ICNS_PropheseeLib.SchLib")
      )
      (libsource (lib "Western Sydney University - ICNS") (part "LT3080IDD-1#TRPBF"))
    )
    (comp (ref "UP5")
      (value "LT3080IDD-1#TRPBF")
      (footprint "LT-DD-8_V")
      (description "Linear Voltage Regulator IC Positive Adjustable 1 Output 1.1A 8-DFN (3x3)")
      (fields
        (field (name "MANUFACTURER") "Analog Devices / Linear Technology")
        (field (name "SOURCE") "ICNS_PropheseeLib.SchLib")
      )
      (libsource (lib "Western Sydney University - ICNS") (part "LT3080IDD-1#TRPBF"))
    )
    (comp (ref "UP6")
      (value "LT3080IDD-1#TRPBF")
      (footprint "LT-DD-8_V")
      (description "Linear Voltage Regulator IC Positive Adjustable 1 Output 1.1A 8-DFN (3x3)")
      (fields
        (field (name "MANUFACTURER") "Analog Devices / Linear Technology")
        (field (name "SOURCE") "ICNS_PropheseeLib.SchLib")
      )
      (libsource (lib "Western Sydney University - ICNS") (part "LT3080IDD-1#TRPBF"))
    )
  )
  (nets
    (net (code "2") (name "5V") (class "Default")
      (node (ref "POWER_IN1") (pin "1") (pinfunction "1_1") (pintype "passive"))
      (node (ref "Q2") (pin "3") (pinfunction "D_3") (pintype "passive"))
    )
    (net (code "3") (name "GND") (class "Default")
      (node (ref "C15") (pin "2") (pinfunction "2_2") (pintype "passive"))
      (node (ref "C16") (pin "2") (pinfunction "2_2") (pintype "passive"))
      (node (ref "C17") (pin "2") (pinfunction "2_2") (pintype "passive"))
      (node (ref "C18") (pin "2") (pinfunction "2_2") (pintype "passive"))
      (node (ref "C19") (pin "2") (pinfunction "2_2") (pintype "passive"))
      (node (ref "C20") (pin "2") (pinfunction "2_2") (pintype "passive"))
      (node (ref "C21") (pin "2") (pinfunction "2_2") (pintype "passive"))
      (node (ref "C22") (pin "1") (pinfunction "1_1") (pintype "passive"))
      (node (ref "C23") (pin "2") (pinfunction "2_2") (pintype "passive"))
      (node (ref "C24") (pin "2") (pinfunction "2_2") (pintype "passive"))
      (node (ref "C25") (pin "2") (pinfunction "2_2") (pintype "passive"))
      (node (ref "C26") (pin "2") (pinfunction "2_2") (pintype "passive"))
      (node (ref "C27") (pin "2") (pinfunction "2_2") (pintype "passive"))
      (node (ref "C28") (pin "2") (pinfunction "2_2") (pintype "passive"))
      (node (ref "C29") (pin "2") (pinfunction "2_2") (pintype "passive"))
      (node (ref "C30") (pin "2") (pinfunction "2_2") (pintype "passive"))
      (node (ref "C32") (pin "2") (pinfunction "2_2") (pintype "passive"))
      (node (ref "C33") (pin "1") (pinfunction "1_1") (pintype "passive"))
      (node (ref "C34") (pin "2") (pinfunction "2_2") (pintype "passive"))
      (node (ref "C35") (pin "2") (pinfunction "2_2") (pintype "passive"))
      (node (ref "C36") (pin "2") (pinfunction "2_2") (pintype "passive"))
      (node (ref "C37") (pin "2") (pinfunction "2_2") (pintype "passive"))
      (node (ref "C38") (pin "2") (pinfunction "2_2") (pintype "passive"))
      (node (ref "C39") (pin "2") (pinfunction "2_2") (pintype "passive"))
      (node (ref "C41") (pin "1") (pinfunction "1_1") (pintype "passive"))
      (node (ref "C42") (pin "2") (pinfunction "2_2") (pintype "passive"))
      (node (ref "C43") (pin "1") (pinfunction "1_1") (pintype "passive"))
      (node (ref "C44") (pin "1") (pinfunction "1_1") (pintype "passive"))
      (node (ref "C45") (pin "1") (pinfunction "1_1") (pintype "passive"))
      (node (ref "C46") (pin "2") (pinfunction "2_2") (pintype "passive"))
      (node (ref "C47") (pin "2") (pinfunction "2_2") (pintype "passive"))
      (node (ref "C48") (pin "2") (pinfunction "2_2") (pintype "passive"))
      (node (ref "C49") (pin "2") (pinfunction "2_2") (pintype "passive"))
      (node (ref "C50") (pin "2") (pinfunction "2_2") (pintype "passive"))
      (node (ref "C52") (pin "2") (pinfunction "2_2") (pintype "passive"))
      (node (ref "C53") (pin "2") (pinfunction "2_2") (pintype "passive"))
      (node (ref "C54") (pin "2") (pinfunction "2_2") (pintype "passive"))
      (node (ref "C55") (pin "1") (pinfunction "1_1") (pintype "passive"))
      (node (ref "D1") (pin "1") (pinfunction "A_1") (pintype "passive"))
      (node (ref "POWER_IN1") (pin "2") (pinfunction "2_2") (pintype "passive"))
      (node (ref "POWER_IN1") (pin "3") (pinfunction "3_3") (pintype "passive"))
      (node (ref "R11") (pin "2") (pinfunction "2_2") (pintype "passive"))
      (node (ref "R12") (pin "2") (pinfunction "2_2") (pintype "passive"))
      (node (ref "R13") (pin "2") (pinfunction "2_2") (pintype "passive"))
      (node (ref "R14") (pin "2") (pinfunction "2_2") (pintype "passive"))
      (node (ref "R18") (pin "2") (pinfunction "2_2") (pintype "passive"))
      (node (ref "R19") (pin "2") (pinfunction "2_2") (pintype "passive"))
      (node (ref "R20") (pin "1") (pinfunction "1_1") (pintype "passive"))
      (node (ref "R22") (pin "2") (pinfunction "2_2") (pintype "passive"))
      (node (ref "R25") (pin "2") (pinfunction "2_2") (pintype "passive"))
      (node (ref "R26") (pin "2") (pinfunction "2_2") (pintype "passive"))
      (node (ref "R30") (pin "2") (pinfunction "2_2") (pintype "passive"))
      (node (ref "R31") (pin "2") (pinfunction "2_2") (pintype "passive"))
      (node (ref "R32") (pin "2") (pinfunction "2_2") (pintype "passive"))
      (node (ref "TP12") (pin "1") (pinfunction "1_1") (pintype "passive"))
      (node (ref "TP13") (pin "1") (pinfunction "1_1") (pintype "passive"))
      (node (ref "TP14") (pin "1") (pinfunction "1_1") (pintype "passive"))
      (node (ref "TP15") (pin "1") (pinfunction "1_1") (pintype "passive"))
      (node (ref "TP16") (pin "1") (pinfunction "1_1") (pintype "passive"))
      (node (ref "UP1") (pin "1") (pinfunction "SRLIM/DDR_1") (pintype "input"))
      (node (ref "UP1") (pin "21") (pinfunction "MODE_21") (pintype "input"))
      (node (ref "UP1") (pin "25") (pinfunction "EP_25") (pintype "power_in"))
      (node (ref "UP1") (pin "3") (pinfunction "SGND_3") (pintype "power_in"))
      (node (ref "UP2") (pin "1") (pinfunction "SRLIM/DDR_1") (pintype "input"))
      (node (ref "UP2") (pin "21") (pinfunction "MODE_21") (pintype "input"))
      (node (ref "UP2") (pin "25") (pinfunction "EP_25") (pintype "power_in"))
      (node (ref "UP2") (pin "3") (pinfunction "SGND_3") (pintype "power_in"))
      (node (ref "UP3") (pin "1") (pinfunction "SRLIM/DDR_1") (pintype "input"))
      (node (ref "UP3") (pin "21") (pinfunction "MODE_21") (pintype "input"))
      (node (ref "UP3") (pin "25") (pinfunction "EP_25") (pintype "power_in"))
      (node (ref "UP3") (pin "3") (pinfunction "SGND_3") (pintype "power_in"))
    )
    (net (code "4") (name "Net-(D1A-K)") (class "Default")
      (node (ref "D1") (pin "3") (pinfunction "K_3") (pintype "passive"))
      (node (ref "R10") (pin "1") (pinfunction "1_1") (pintype "passive"))
      (node (ref "R8") (pin "2") (pinfunction "2_2") (pintype "passive"))
    )
    (net (code "5") (name "Net-(D2-K)") (class "Default")
      (node (ref "D2") (pin "1") (pinfunction "K_1") (pintype "passive"))
      (node (ref "R31") (pin "1") (pinfunction "1_1") (pintype "passive"))
    )
    (net (code "6") (name "Net-(D3-K)") (class "Default")
      (node (ref "D3") (pin "1") (pinfunction "K_1") (pintype "passive"))
      (node (ref "R32") (pin "1") (pinfunction "1_1") (pintype "passive"))
    )
    (net (code "7") (name "Net-(L2-Pad1)") (class "Default")
      (node (ref "L2") (pin "1") (pinfunction "1_1") (pintype "passive"))
      (node (ref "UP3") (pin "13") (pinfunction "SW_13") (pintype "power_in"))
      (node (ref "UP3") (pin "14") (pinfunction "SW_14") (pintype "power_in"))
      (node (ref "UP3") (pin "15") (pinfunction "SW_15") (pintype "power_in"))
      (node (ref "UP3") (pin "16") (pinfunction "SW_16") (pintype "power_in"))
      (node (ref "UP3") (pin "5") (pinfunction "SW_5") (pintype "power_in"))
      (node (ref "UP3") (pin "6") (pinfunction "SW_6") (pintype "power_in"))
      (node (ref "UP3") (pin "7") (pinfunction "SW_7") (pintype "power_in"))
      (node (ref "UP3") (pin "8") (pinfunction "SW_8") (pintype "power_in"))
    )
    (net (code "8") (name "Net-(L3-Pad1)") (class "Default")
      (node (ref "L3") (pin "1") (pinfunction "1_1") (pintype "passive"))
      (node (ref "UP2") (pin "13") (pinfunction "SW_13") (pintype "power_in"))
      (node (ref "UP2") (pin "14") (pinfunction "SW_14") (pintype "power_in"))
      (node (ref "UP2") (pin "15") (pinfunction "SW_15") (pintype "power_in"))
      (node (ref "UP2") (pin "16") (pinfunction "SW_16") (pintype "power_in"))
      (node (ref "UP2") (pin "5") (pinfunction "SW_5") (pintype "power_in"))
      (node (ref "UP2") (pin "6") (pinfunction "SW_6") (pintype "power_in"))
      (node (ref "UP2") (pin "7") (pinfunction "SW_7") (pintype "power_in"))
      (node (ref "UP2") (pin "8") (pinfunction "SW_8") (pintype "power_in"))
    )
    (net (code "9") (name "Net-(L4-Pad1)") (class "Default")
      (node (ref "L4") (pin "1") (pinfunction "1_1") (pintype "passive"))
      (node (ref "UP1") (pin "13") (pinfunction "SW_13") (pintype "power_in"))
      (node (ref "UP1") (pin "14") (pinfunction "SW_14") (pintype "power_in"))
      (node (ref "UP1") (pin "15") (pinfunction "SW_15") (pintype "power_in"))
      (node (ref "UP1") (pin "16") (pinfunction "SW_16") (pintype "power_in"))
      (node (ref "UP1") (pin "5") (pinfunction "SW_5") (pintype "power_in"))
      (node (ref "UP1") (pin "6") (pinfunction "SW_6") (pintype "power_in"))
      (node (ref "UP1") (pin "7") (pinfunction "SW_7") (pintype "power_in"))
      (node (ref "UP1") (pin "8") (pinfunction "SW_8") (pintype "power_in"))
    )
    (net (code "10") (name "Net-(Q2-G)") (class "Default")
      (node (ref "Q2") (pin "1") (pinfunction "G_1") (pintype "passive"))
      (node (ref "R12") (pin "1") (pinfunction "1_1") (pintype "passive"))
      (node (ref "R7") (pin "2") (pinfunction "2_2") (pintype "passive"))
    )
    (net (code "11") (name "Net-(Q2-S)") (class "Default")
      (node (ref "Q2") (pin "2") (pinfunction "S_2") (pintype "passive"))
      (node (ref "Q3") (pin "2") (pinfunction "E_2") (pintype "passive"))
      (node (ref "Q4") (pin "2") (pinfunction "S_2") (pintype "passive"))
      (node (ref "R7") (pin "1") (pinfunction "1_1") (pintype "passive"))
      (node (ref "R8") (pin "1") (pinfunction "1_1") (pintype "passive"))
      (node (ref "R9") (pin "1") (pinfunction "1_1") (pintype "passive"))
    )
    (net (code "12") (name "Net-(Q3-B)") (class "Default")
      (node (ref "Q3") (pin "1") (pinfunction "B_1") (pintype "passive"))
      (node (ref "R10") (pin "2") (pinfunction "2_2") (pintype "passive"))
    )
    (net (code "13") (name "Net-(Q3-C)") (class "Default")
      (node (ref "Q3") (pin "3") (pinfunction "C_3") (pintype "passive"))
      (node (ref "Q4") (pin "1") (pinfunction "G_1") (pintype "passive"))
      (node (ref "R13") (pin "1") (pinfunction "1_1") (pintype "passive"))
      (node (ref "R9") (pin "2") (pinfunction "2_2") (pintype "passive"))
    )
    (net (code "14") (name "Net-(UP1-PGOOD)") (class "Default")
      (node (ref "R28") (pin "1") (pinfunction "1_1") (pintype "passive"))
      (node (ref "UP1") (pin "20") (pinfunction "PGOOD_20") (pintype "open_collector"))
    )
    (net (code "15") (name "Net-(UP1-RUN)") (class "Default")
      (node (ref "R29") (pin "1") (pinfunction "1_1") (pintype "passive"))
      (node (ref "UP1") (pin "19") (pinfunction "RUN_19") (pintype "input"))
    )
    (net (code "16") (name "Net-(UP1-VFB)") (class "Default")
      (node (ref "C51") (pin "2") (pinfunction "2_2") (pintype "passive"))
      (node (ref "R27") (pin "2") (pinfunction "2_2") (pintype "passive"))
      (node (ref "R30") (pin "1") (pinfunction "1_1") (pintype "passive"))
      (node (ref "UP1") (pin "22") (pinfunction "VFB_22") (pintype "input"))
    )
    (net (code "17") (name "Net-(UP2-PGOOD)") (class "Default")
      (node (ref "R23") (pin "1") (pinfunction "1_1") (pintype "passive"))
      (node (ref "UP2") (pin "20") (pinfunction "PGOOD_20") (pintype "open_collector"))
    )
    (net (code "18") (name "Net-(UP2-RUN)") (class "Default")
      (node (ref "R24") (pin "1") (pinfunction "1_1") (pintype "passive"))
      (node (ref "UP2") (pin "19") (pinfunction "RUN_19") (pintype "input"))
    )
    (net (code "19") (name "Net-(UP2-VFB)") (class "Default")
      (node (ref "C40") (pin "2") (pinfunction "2_2") (pintype "passive"))
      (node (ref "R21") (pin "2") (pinfunction "2_2") (pintype "passive"))
      (node (ref "R26") (pin "1") (pinfunction "1_1") (pintype "passive"))
      (node (ref "UP2") (pin "22") (pinfunction "VFB_22") (pintype "input"))
    )
    (net (code "20") (name "Net-(UP3-PGOOD)") (class "Default")
      (node (ref "R16") (pin "1") (pinfunction "1_1") (pintype "passive"))
      (node (ref "UP3") (pin "20") (pinfunction "PGOOD_20") (pintype "open_collector"))
    )
    (net (code "21") (name "Net-(UP3-RUN)") (class "Default")
      (node (ref "R17") (pin "1") (pinfunction "1_1") (pintype "passive"))
      (node (ref "UP3") (pin "19") (pinfunction "RUN_19") (pintype "input"))
    )
    (net (code "22") (name "Net-(UP3-VFB)") (class "Default")
      (node (ref "C31") (pin "2") (pinfunction "2_2") (pintype "passive"))
      (node (ref "R15") (pin "2") (pinfunction "2_2") (pintype "passive"))
      (node (ref "R19") (pin "1") (pinfunction "1_1") (pintype "passive"))
      (node (ref "UP3") (pin "22") (pinfunction "VFB_22") (pintype "input"))
    )
    (net (code "23") (name "Net-(UP4-SET)") (class "Default")
      (node (ref "C46") (pin "1") (pinfunction "1_1") (pintype "passive"))
      (node (ref "C47") (pin "1") (pinfunction "1_1") (pintype "passive"))
      (node (ref "R25") (pin "1") (pinfunction "1_1") (pintype "passive"))
      (node (ref "UP4") (pin "4") (pinfunction "SET_4") (pintype "input"))
    )
    (net (code "24") (name "Net-(UP5-SET)") (class "Default")
      (node (ref "C34") (pin "1") (pinfunction "1_1") (pintype "passive"))
      (node (ref "C35") (pin "1") (pinfunction "1_1") (pintype "passive"))
      (node (ref "R20") (pin "2") (pinfunction "2_2") (pintype "passive"))
      (node (ref "UP5") (pin "4") (pinfunction "SET_4") (pintype "input"))
    )
    (net (code "25") (name "Net-(UP6-SET)") (class "Default")
      (node (ref "C23") (pin "1") (pinfunction "1_1") (pintype "passive"))
      (node (ref "C24") (pin "1") (pinfunction "1_1") (pintype "passive"))
      (node (ref "R14") (pin "1") (pinfunction "1_1") (pintype "passive"))
      (node (ref "UP6") (pin "4") (pinfunction "SET_4") (pintype "input"))
    )
    (net (code "26") (name "VCC1P1") (class "Default")
      (node (ref "C29") (pin "1") (pinfunction "1_1") (pintype "passive"))
      (node (ref "C30") (pin "1") (pinfunction "1_1") (pintype "passive"))
      (node (ref "C31") (pin "1") (pinfunction "1_1") (pintype "passive"))
      (node (ref "FB4") (pin "1") (pinfunction "1_1") (pintype "passive"))
      (node (ref "L2") (pin "2") (pinfunction "2_2") (pintype "passive"))
      (node (ref "R15") (pin "1") (pinfunction "1_1") (pintype "passive"))
      (node (ref "TP3") (pin "1") (pinfunction "1_1") (pintype "passive"))
    )
    (net (code "27") (name "VCC1P1_HPS") (class "Default")
      (node (ref "FB4") (pin "2") (pinfunction "2_2") (pintype "passive"))
    )
    (net (code "28") (name "VCC1P2") (class "Default")
      (node (ref "C41") (pin "2") (pinfunction "2_2") (pintype "passive"))
      (node (ref "R22") (pin "1") (pinfunction "1_1") (pintype "passive"))
      (node (ref "TP6") (pin "1") (pinfunction "1_1") (pintype "passive"))
      (node (ref "UP4") (pin "1") (pinfunction "OUT_1") (pintype "power_in"))
      (node (ref "UP4") (pin "2") (pinfunction "OUT_2") (pintype "power_in"))
      (node (ref "UP4") (pin "3") (pinfunction "OUT_3") (pintype "power_in"))
      (node (ref "UP4") (pin "9") (pinfunction "EP_9") (pintype "power_in"))
    )
    (net (code "29") (name "VCC1P5_DDR3") (class "Default")
      (node (ref "C33") (pin "2") (pinfunction "2_2") (pintype "passive"))
      (node (ref "R18") (pin "1") (pinfunction "1_1") (pintype "passive"))
      (node (ref "TP4") (pin "1") (pinfunction "1_1") (pintype "passive"))
      (node (ref "UP5") (pin "1") (pinfunction "OUT_1") (pintype "power_in"))
      (node (ref "UP5") (pin "2") (pinfunction "OUT_2") (pintype "power_in"))
      (node (ref "UP5") (pin "3") (pinfunction "OUT_3") (pintype "power_in"))
      (node (ref "UP5") (pin "9") (pinfunction "EP_9") (pintype "power_in"))
    )
    (net (code "30") (name "VCC1P8") (class "Default")
      (node (ref "C22") (pin "2") (pinfunction "2_2") (pintype "passive"))
      (node (ref "R11") (pin "1") (pinfunction "1_1") (pintype "passive"))
      (node (ref "TP2") (pin "1") (pinfunction "1_1") (pintype "passive"))
      (node (ref "UP6") (pin "1") (pinfunction "OUT_1") (pintype "power_in"))
      (node (ref "UP6") (pin "2") (pinfunction "OUT_2") (pintype "power_in"))
      (node (ref "UP6") (pin "3") (pinfunction "OUT_3") (pintype "power_in"))
      (node (ref "UP6") (pin "9") (pinfunction "EP_9") (pintype "power_in"))
    )
    (net (code "31") (name "VCC2P5") (class "Default")
      (node (ref "C21") (pin "1") (pinfunction "1_1") (pintype "passive"))
      (node (ref "C32") (pin "1") (pinfunction "1_1") (pintype "passive"))
      (node (ref "C36") (pin "1") (pinfunction "1_1") (pintype "passive"))
      (node (ref "C48") (pin "1") (pinfunction "1_1") (pintype "passive"))
      (node (ref "C49") (pin "1") (pinfunction "1_1") (pintype "passive"))
      (node (ref "C50") (pin "1") (pinfunction "1_1") (pintype "passive"))
      (node (ref "C51") (pin "1") (pinfunction "1_1") (pintype "passive"))
      (node (ref "D2") (pin "2") (pinfunction "A_2") (pintype "passive"))
      (node (ref "L4") (pin "2") (pinfunction "2_2") (pintype "passive"))
      (node (ref "R27") (pin "1") (pinfunction "1_1") (pintype "passive"))
      (node (ref "TP7") (pin "1") (pinfunction "1_1") (pintype "passive"))
      (node (ref "UP4") (pin "5") (pinfunction "VCONTROL_5") (pintype "power_in"))
      (node (ref "UP4") (pin "6") (pinfunction "NC_6") (pintype "passive"))
      (node (ref "UP4") (pin "7") (pinfunction "IN_7") (pintype "power_in"))
      (node (ref "UP4") (pin "8") (pinfunction "IN_8") (pintype "power_in"))
      (node (ref "UP5") (pin "5") (pinfunction "VCONTROL_5") (pintype "power_in"))
      (node (ref "UP5") (pin "6") (pinfunction "NC_6") (pintype "passive"))
      (node (ref "UP5") (pin "7") (pinfunction "IN_7") (pintype "power_in"))
      (node (ref "UP5") (pin "8") (pinfunction "IN_8") (pintype "power_in"))
      (node (ref "UP6") (pin "5") (pinfunction "VCONTROL_5") (pintype "power_in"))
      (node (ref "UP6") (pin "6") (pinfunction "NC_6") (pintype "passive"))
      (node (ref "UP6") (pin "7") (pinfunction "IN_7") (pintype "power_in"))
      (node (ref "UP6") (pin "8") (pinfunction "IN_8") (pintype "power_in"))
    )
    (net (code "32") (name "VCC3P3") (class "Default")
      (node (ref "C37") (pin "1") (pinfunction "1_1") (pintype "passive"))
      (node (ref "C38") (pin "1") (pinfunction "1_1") (pintype "passive"))
      (node (ref "C39") (pin "1") (pinfunction "1_1") (pintype "passive"))
      (node (ref "C40") (pin "1") (pinfunction "1_1") (pintype "passive"))
      (node (ref "D3") (pin "2") (pinfunction "A_2") (pintype "passive"))
      (node (ref "L3") (pin "2") (pinfunction "2_2") (pintype "passive"))
      (node (ref "R21") (pin "1") (pinfunction "1_1") (pintype "passive"))
      (node (ref "TP5") (pin "1") (pinfunction "1_1") (pintype "passive"))
    )
    (net (code "33") (name "VCC5") (class "Default")
      (node (ref "C15") (pin "1") (pinfunction "1_1") (pintype "passive"))
      (node (ref "C16") (pin "1") (pinfunction "1_1") (pintype "passive"))
      (node (ref "C17") (pin "1") (pinfunction "1_1") (pintype "passive"))
      (node (ref "C18") (pin "1") (pinfunction "1_1") (pintype "passive"))
      (node (ref "C19") (pin "1") (pinfunction "1_1") (pintype "passive"))
      (node (ref "C20") (pin "1") (pinfunction "1_1") (pintype "passive"))
      (node (ref "C25") (pin "1") (pinfunction "1_1") (pintype "passive"))
      (node (ref "C26") (pin "1") (pinfunction "1_1") (pintype "passive"))
      (node (ref "C27") (pin "1") (pinfunction "1_1") (pintype "passive"))
      (node (ref "C28") (pin "1") (pinfunction "1_1") (pintype "passive"))
      (node (ref "C42") (pin "1") (pinfunction "1_1") (pintype "passive"))
      (node (ref "C43") (pin "2") (pinfunction "2_2") (pintype "passive"))
      (node (ref "C44") (pin "2") (pinfunction "2_2") (pintype "passive"))
      (node (ref "C45") (pin "2") (pinfunction "2_2") (pintype "passive"))
      (node (ref "C52") (pin "1") (pinfunction "1_1") (pintype "passive"))
      (node (ref "C53") (pin "1") (pinfunction "1_1") (pintype "passive"))
      (node (ref "C54") (pin "1") (pinfunction "1_1") (pintype "passive"))
      (node (ref "C55") (pin "2") (pinfunction "2_2") (pintype "passive"))
      (node (ref "Q4") (pin "3") (pinfunction "D_3") (pintype "passive"))
      (node (ref "R16") (pin "2") (pinfunction "2_2") (pintype "passive"))
      (node (ref "R17") (pin "2") (pinfunction "2_2") (pintype "passive"))
      (node (ref "R23") (pin "2") (pinfunction "2_2") (pintype "passive"))
      (node (ref "R24") (pin "2") (pinfunction "2_2") (pintype "passive"))
      (node (ref "R28") (pin "2") (pinfunction "2_2") (pintype "passive"))
      (node (ref "R29") (pin "2") (pinfunction "2_2") (pintype "passive"))
      (node (ref "TP1") (pin "1") (pinfunction "1_1") (pintype "passive"))
      (node (ref "UP1") (pin "10") (pinfunction "PVIN_10") (pintype "power_in"))
      (node (ref "UP1") (pin "11") (pinfunction "PVIN_11") (pintype "power_in"))
      (node (ref "UP1") (pin "17") (pinfunction "PVIN_17") (pintype "power_in"))
      (node (ref "UP1") (pin "18") (pinfunction "SVIN_18") (pintype "power_in"))
      (node (ref "UP1") (pin "2") (pinfunction "RT/SYNC_2") (pintype "input"))
      (node (ref "UP1") (pin "23") (pinfunction "ITH_23") (pintype "passive"))
      (node (ref "UP1") (pin "24") (pinfunction "TRACK/SS_24") (pintype "input"))
      (node (ref "UP1") (pin "4") (pinfunction "PVIN_4") (pintype "power_in"))
      (node (ref "UP2") (pin "10") (pinfunction "PVIN_10") (pintype "power_in"))
      (node (ref "UP2") (pin "11") (pinfunction "PVIN_11") (pintype "power_in"))
      (node (ref "UP2") (pin "17") (pinfunction "PVIN_17") (pintype "power_in"))
      (node (ref "UP2") (pin "18") (pinfunction "SVIN_18") (pintype "power_in"))
      (node (ref "UP2") (pin "2") (pinfunction "RT/SYNC_2") (pintype "input"))
      (node (ref "UP2") (pin "23") (pinfunction "ITH_23") (pintype "passive"))
      (node (ref "UP2") (pin "24") (pinfunction "TRACK/SS_24") (pintype "input"))
      (node (ref "UP2") (pin "4") (pinfunction "PVIN_4") (pintype "power_in"))
      (node (ref "UP3") (pin "10") (pinfunction "PVIN_10") (pintype "power_in"))
      (node (ref "UP3") (pin "11") (pinfunction "PVIN_11") (pintype "power_in"))
      (node (ref "UP3") (pin "17") (pinfunction "PVIN_17") (pintype "power_in"))
      (node (ref "UP3") (pin "18") (pinfunction "SVIN_18") (pintype "power_in"))
      (node (ref "UP3") (pin "2") (pinfunction "RT/SYNC_2") (pintype "input"))
      (node (ref "UP3") (pin "23") (pinfunction "ITH_23") (pintype "passive"))
      (node (ref "UP3") (pin "24") (pinfunction "TRACK/SS_24") (pintype "input"))
      (node (ref "UP3") (pin "4") (pinfunction "PVIN_4") (pintype "power_in"))
    )
    (net (code "34") (name "unconnected-(D1B-NC-Pad2)") (class "Default")
      (node (ref "D1") (pin "2") (pinfunction "NC_2") (pintype "passive+no_connect"))
    )
    (net (code "35") (name "unconnected-(H5-Pad0)") (class "Default")
      (node (ref "H5") (pin "0") (pinfunction "0_0") (pintype "passive"))
    )
    (net (code "36") (name "unconnected-(H6-Pad0)") (class "Default")
      (node (ref "H6") (pin "0") (pinfunction "0_0") (pintype "passive"))
    )
    (net (code "37") (name "unconnected-(H7-Pad0)") (class "Default")
      (node (ref "H7") (pin "0") (pinfunction "0_0") (pintype "passive"))
    )
    (net (code "38") (name "unconnected-(H8-Pad0)") (class "Default")
      (node (ref "H8") (pin "0") (pinfunction "0_0") (pintype "passive"))
    )
    (net (code "39") (name "unconnected-(UP1-NC-Pad9)") (class "Default")
      (node (ref "UP1") (pin "9") (pinfunction "NC_9") (pintype "passive+no_connect"))
    )
    (net (code "40") (name "unconnected-(UP1-NC-Pad12)") (class "Default")
      (node (ref "UP1") (pin "12") (pinfunction "NC_12") (pintype "passive+no_connect"))
    )
    (net (code "41") (name "unconnected-(UP2-NC-Pad9)") (class "Default")
      (node (ref "UP2") (pin "9") (pinfunction "NC_9") (pintype "passive+no_connect"))
    )
    (net (code "42") (name "unconnected-(UP2-NC-Pad12)") (class "Default")
      (node (ref "UP2") (pin "12") (pinfunction "NC_12") (pintype "passive+no_connect"))
    )
    (net (code "43") (name "unconnected-(UP3-NC-Pad9)") (class "Default")
      (node (ref "UP3") (pin "9") (pinfunction "NC_9") (pintype "passive+no_connect"))
    )
    (net (code "44") (name "unconnected-(UP3-NC-Pad12)") (class "Default")
      (node (ref "UP3") (pin "12") (pinfunction "NC_12") (pintype "passive+no_connect"))
    )
  )
)
